# iox.net
KiCad netlist of a schematic drawn in Altium Designer
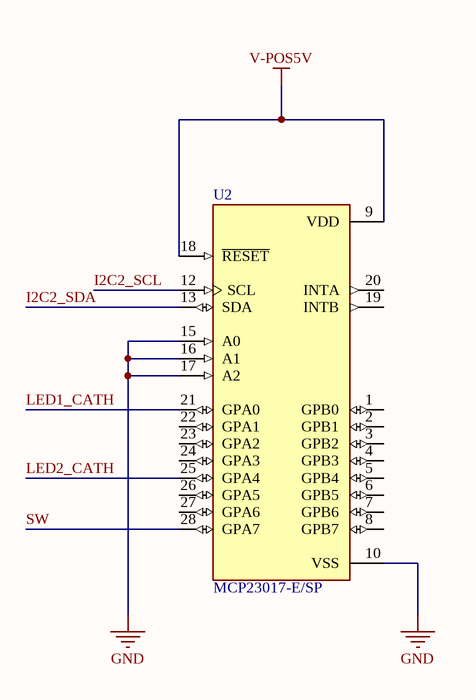
[diagram p0: iox.SchDoc]

(export (version "E")
  (design (tool "Eeschema 10.0.6"))
  (components
    (comp (ref "U2")
      (value "MCP23017-E/SP")
      (footprint "DIP787W45P254L3556H508Q28")
      (description "I/O Expander 16 IÂ²C 1.7MHz 28-SPDIP")
      (fields (field (name "MF") "Microchip"))
      (libsource (lib "firmware_tutorial_board") (part "MCP23017-E/SP"))
    )
  )
  (nets
    (net (code "1") (name "/I2C2_SCL") (class "Default")
      (node (ref "U2") (pin "12") (pinfunction "SCL_12") (pintype "input"))
    )
    (net (code "2") (name "/I2C2_SDA") (class "Default")
      (node (ref "U2") (pin "13") (pinfunction "SDA_13") (pintype "bidirectional"))
    )
    (net (code "3") (name "/LED1_CATH") (class "Default")
      (node (ref "U2") (pin "21") (pinfunction "GPA0_21") (pintype "bidirectional"))
    )
    (net (code "4") (name "/LED2_CATH") (class "Default")
      (node (ref "U2") (pin "25") (pinfunction "GPA4_25") (pintype "bidirectional"))
    )
    (net (code "5") (name "/SW") (class "Default")
      (node (ref "U2") (pin "28") (pinfunction "GPA7_28") (pintype "bidirectional"))
    )
    (net (code "6") (name "GND") (class "Default")
      (node (ref "U2") (pin "10") (pinfunction "VSS_10") (pintype "power_in"))
      (node (ref "U2") (pin "15") (pinfunction "A0_15") (pintype "input"))
      (node (ref "U2") (pin "16") (pinfunction "A1_16") (pintype "input"))
      (node (ref "U2") (pin "17") (pinfunction "A2_17") (pintype "input"))
    )
    (net (code "7") (name "V-POS5V") (class "Default")
      (node (ref "U2") (pin "18") (pinfunction "~{RESET}_18") (pintype "input"))
      (node (ref "U2") (pin "9") (pinfunction "VDD_9") (pintype "power_in"))
    )
    (net (code "8") (name "unconnected-(U2-GPA1-Pad22)") (class "Default")
      (node (ref "U2") (pin "22") (pinfunction "GPA1_22") (pintype "bidirectional"))
    )
    (net (code "9") (name "unconnected-(U2-GPA2-Pad23)") (class "Default")
      (node (ref "U2") (pin "23") (pinfunction "GPA2_23") (pintype "bidirectional"))
    )
    (net (code "10") (name "unconnected-(U2-GPA3-Pad24)") (class "Default")
      (node (ref "U2") (pin "24") (pinfunction "GPA3_24") (pintype "bidirectional"))
    )
    (net (code "11") (name "unconnected-(U2-GPA5-Pad26)") (class "Default")
      (node (ref "U2") (pin "26") (pinfunction "GPA5_26") (pintype "bidirectional"))
    )
    (net (code "12") (name "unconnected-(U2-GPA6-Pad27)") (class "Default")
      (node (ref "U2") (pin "27") (pinfunction "GPA6_27") (pintype "bidirectional"))
    )
    (net (code "13") (name "unconnected-(U2-GPB0-Pad1)") (class "Default")
      (node (ref "U2") (pin "1") (pinfunction "GPB0_1") (pintype "bidirectional"))
    )
    (net (code "14") (name "unconnected-(U2-GPB1-Pad2)") (class "Default")
      (node (ref "U2") (pin "2") (pinfunction "GPB1_2") (pintype "bidirectional"))
    )
    (net (code "15") (name "unconnected-(U2-GPB2-Pad3)") (class "Default")
      (node (ref "U2") (pin "3") (pinfunction "GPB2_3") (pintype "bidirectional"))
    )
    (net (code "16") (name "unconnected-(U2-GPB3-Pad4)") (class "Default")
      (node (ref "U2") (pin "4") (pinfunction "GPB3_4") (pintype "bidirectional"))
    )
    (net (code "17") (name "unconnected-(U2-GPB4-Pad5)") (class "Default")
      (node (ref "U2") (pin "5") (pinfunction "GPB4_5") (pintype "bidirectional"))
    )
    (net (code "18") (name "unconnected-(U2-GPB5-Pad6)") (class "Default")
      (node (ref "U2") (pin "6") (pinfunction "GPB5_6") (pintype "bidirectional"))
    )
    (net (code "19") (name "unconnected-(U2-GPB6-Pad7)") (class "Default")
      (node (ref "U2") (pin "7") (pinfunction "GPB6_7") (pintype "bidirectional"))
    )
    (net (code "20") (name "unconnected-(U2-GPB7-Pad8)") (class "Default")
      (node (ref "U2") (pin "8") (pinfunction "GPB7_8") (pintype "bidirectional"))
    )
    (net (code "21") (name "unconnected-(U2-INTA-Pad20)") (class "Default")
      (node (ref "U2") (pin "20") (pinfunction "INTA_20") (pintype "output"))
    )
    (net (code "22") (name "unconnected-(U2-INTB-Pad19)") (class "Default")
      (node (ref "U2") (pin "19") (pinfunction "INTB_19") (pintype "output"))
    )
  )
)
